# Sheet_1.net
KiCad netlist of a schematic drawn in EasyEDA
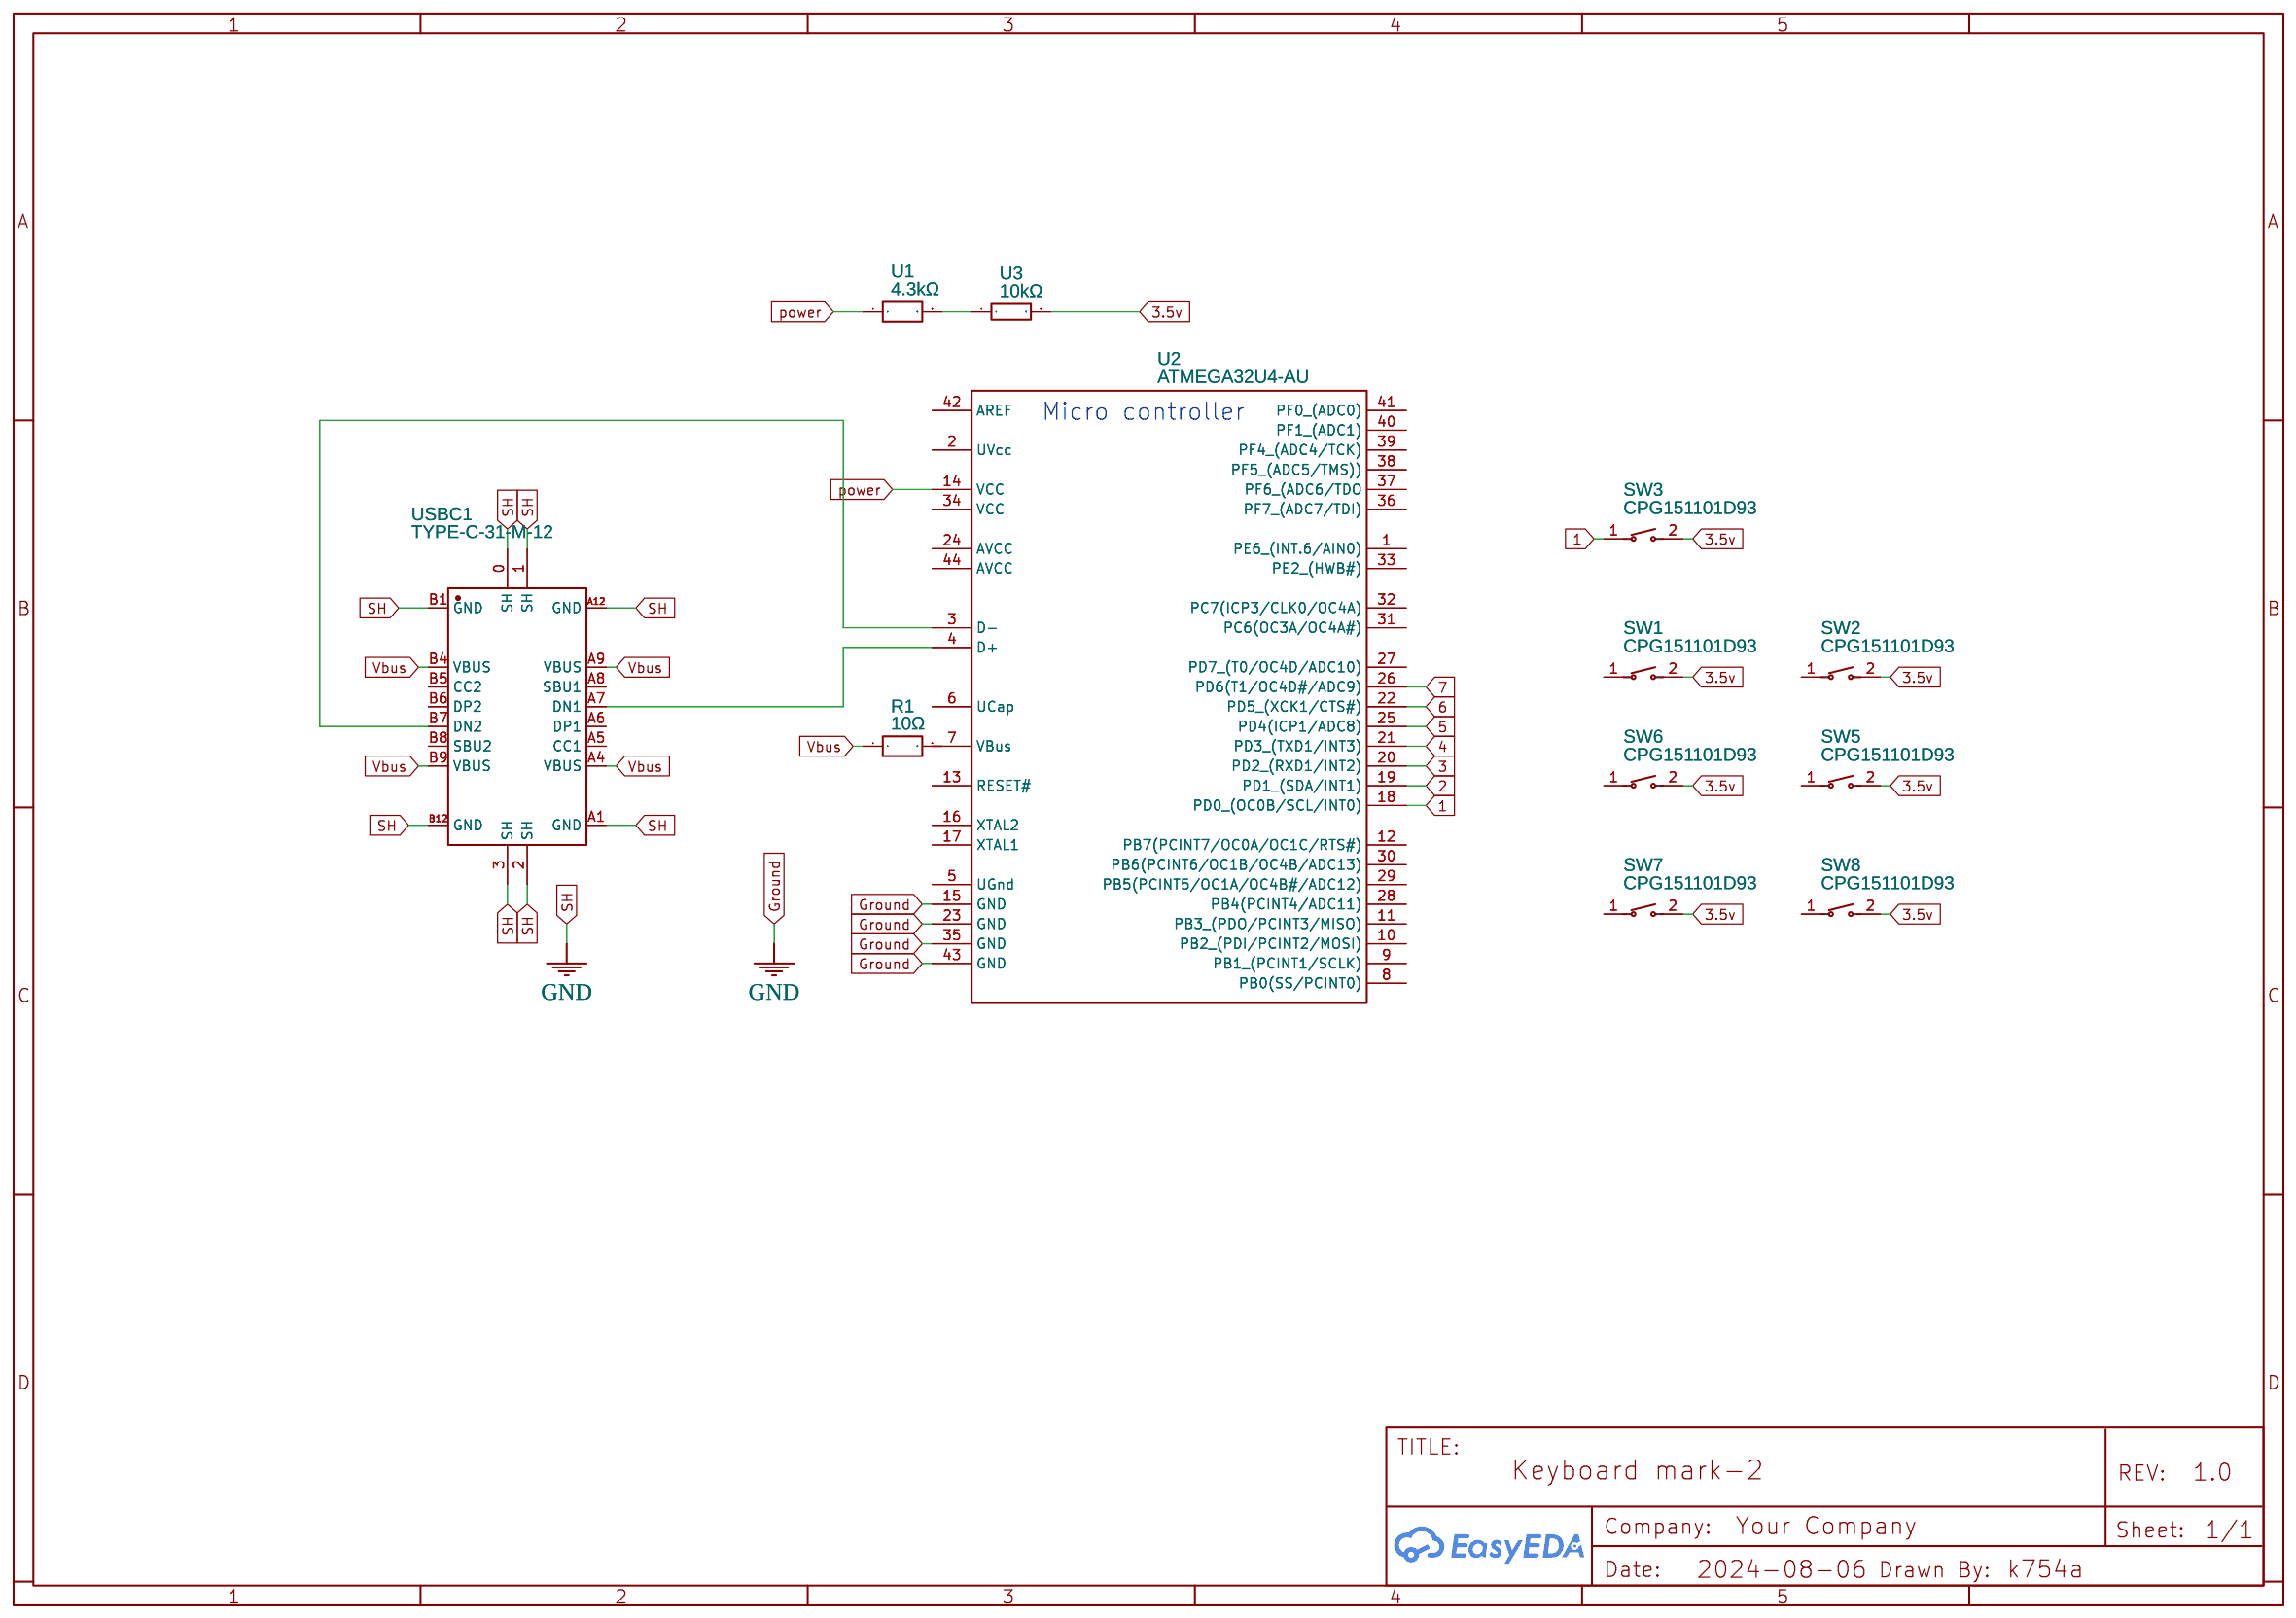
[diagram p0: schematic sheet]

(export (version "E")
  (design (tool "Eeschema 10.0.6"))
  (components
    (comp (ref "R1")
      (value "10Ω")
      (fields (field (name "Manufacturer Part") "CR1W-4K7±5%-TT63") (field (name "Manufacturer") "VO(翔胜)"))
      (libsource (lib "") (part "10Ω_1W"))
    )
    (comp (ref "SW1")
      (value "CPG151101D93")
      (fields (field (name "Manufacturer") "Kailh(凯华)"))
      (libsource (lib "") (part "CPG151101D93"))
    )
    (comp (ref "SW2")
      (value "CPG151101D93")
      (fields (field (name "Manufacturer") "Kailh(凯华)"))
      (libsource (lib "") (part "CPG151101D93"))
    )
    (comp (ref "SW3")
      (value "CPG151101D93")
      (fields (field (name "Manufacturer") "Kailh(凯华)"))
      (libsource (lib "") (part "CPG151101D93"))
    )
    (comp (ref "SW5")
      (value "CPG151101D93")
      (fields (field (name "Manufacturer") "Kailh(凯华)"))
      (libsource (lib "") (part "CPG151101D93"))
    )
    (comp (ref "SW6")
      (value "CPG151101D93")
      (fields (field (name "Manufacturer") "Kailh(凯华)"))
      (libsource (lib "") (part "CPG151101D93"))
    )
    (comp (ref "SW7")
      (value "CPG151101D93")
      (fields (field (name "Manufacturer") "Kailh(凯华)"))
      (libsource (lib "") (part "CPG151101D93"))
    )
    (comp (ref "SW8")
      (value "CPG151101D93")
      (fields (field (name "Manufacturer") "Kailh(凯华)"))
      (libsource (lib "") (part "CPG151101D93"))
    )
    (comp (ref "U1")
      (value "4.3kΩ")
      (fields (field (name "Manufacturer Part") "CR1/8W-4K3±5%-OT52") (field (name "Manufacturer") "VO(翔胜)"))
      (libsource (lib "") (part "CR1/8W-4K3±5%-OT52"))
    )
    (comp (ref "U2")
      (value "ATMEGA32U4-AU")
      (fields (field (name "Manufacturer") "MICROCHIP(美国微芯)"))
      (libsource (lib "") (part "ATMEGA32U4-AU"))
    )
    (comp (ref "U3")
      (value "10kΩ")
      (fields (field (name "Manufacturer Part") "HV73V1JTTD1002F") (field (name "Manufacturer") "KOA"))
      (libsource (lib "") (part "HV73V1JTTD1002F"))
    )
    (comp (ref "USBC1")
      (value "TYPE-C-31-M-12")
      (fields (field (name "Manufacturer") "韩国韩荣"))
      (libsource (lib "") (part "TYPE-C-31-M-12"))
    )
  )
  (nets
    (net (code "1") (name "1") (class "Default")
      (node (ref "SW3") (pin "1") (pinfunction "1_1") (pintype "unspecified"))
      (node (ref "U2") (pin "18") (pinfunction "PD0_(OC0B/SCL/INT0)_18") (pintype "bidirectional"))
    )
    (net (code "2") (name "2") (class "Default")
      (node (ref "U2") (pin "19") (pinfunction "PD1_(SDA/INT1)_19") (pintype "bidirectional"))
    )
    (net (code "3") (name "3") (class "Default")
      (node (ref "U2") (pin "20") (pinfunction "PD2_(RXD1/INT2)_20") (pintype "bidirectional"))
    )
    (net (code "4") (name "3.5v") (class "Default")
      (node (ref "SW1") (pin "2") (pinfunction "2_2") (pintype "unspecified"))
      (node (ref "SW2") (pin "2") (pinfunction "2_2") (pintype "unspecified"))
      (node (ref "SW3") (pin "2") (pinfunction "2_2") (pintype "unspecified"))
      (node (ref "SW5") (pin "2") (pinfunction "2_2") (pintype "unspecified"))
      (node (ref "SW6") (pin "2") (pinfunction "2_2") (pintype "unspecified"))
      (node (ref "SW7") (pin "2") (pinfunction "2_2") (pintype "unspecified"))
      (node (ref "SW8") (pin "2") (pinfunction "2_2") (pintype "unspecified"))
      (node (ref "U3") (pin "2") (pinfunction "2_2") (pintype "unspecified"))
    )
    (net (code "5") (name "4") (class "Default")
      (node (ref "U2") (pin "21") (pinfunction "PD3_(TXD1/INT3)_21") (pintype "bidirectional"))
    )
    (net (code "6") (name "5") (class "Default")
      (node (ref "U2") (pin "25") (pinfunction "PD4(ICP1/ADC8)_25") (pintype "bidirectional"))
    )
    (net (code "7") (name "6") (class "Default")
      (node (ref "U2") (pin "22") (pinfunction "PD5_(XCK1/CTS#)_22") (pintype "bidirectional"))
    )
    (net (code "8") (name "7") (class "Default")
      (node (ref "U2") (pin "26") (pinfunction "PD6(T1/OC4D#/ADC9)_26") (pintype "bidirectional"))
    )
    (net (code "9") (name "Ground") (class "Default")
      (node (ref "U2") (pin "15") (pinfunction "GND_15") (pintype "passive"))
      (node (ref "U2") (pin "23") (pinfunction "GND_23") (pintype "passive"))
      (node (ref "U2") (pin "35") (pinfunction "GND_35") (pintype "passive"))
      (node (ref "U2") (pin "43") (pinfunction "GND_43") (pintype "passive"))
      (node (ref "USBC1") (pin "0") (pinfunction "SH_0") (pintype "unspecified"))
      (node (ref "USBC1") (pin "1") (pinfunction "SH_1") (pintype "unspecified"))
      (node (ref "USBC1") (pin "2") (pinfunction "SH_2") (pintype "unspecified"))
      (node (ref "USBC1") (pin "3") (pinfunction "SH_3") (pintype "unspecified"))
      (node (ref "USBC1") (pin "A1") (pinfunction "GND_A1") (pintype "unspecified"))
      (node (ref "USBC1") (pin "A12") (pinfunction "GND_A12") (pintype "unspecified"))
      (node (ref "USBC1") (pin "B1") (pinfunction "GND_B1") (pintype "unspecified"))
      (node (ref "USBC1") (pin "B12") (pinfunction "GND_B12") (pintype "unspecified"))
    )
    (net (code "10") (name "Net-(U1-Pad2)") (class "Default")
      (node (ref "U1") (pin "2") (pinfunction "2_2") (pintype "unspecified"))
      (node (ref "U3") (pin "1") (pinfunction "1_1") (pintype "unspecified"))
    )
    (net (code "11") (name "Net-(U2-D+)") (class "Default")
      (node (ref "U2") (pin "4") (pinfunction "D+_4") (pintype "bidirectional"))
      (node (ref "USBC1") (pin "A7") (pinfunction "DN1_A7") (pintype "unspecified"))
    )
    (net (code "12") (name "Net-(U2-D-)") (class "Default")
      (node (ref "U2") (pin "3") (pinfunction "D-_3") (pintype "bidirectional"))
      (node (ref "USBC1") (pin "B7") (pinfunction "DN2_B7") (pintype "unspecified"))
    )
    (net (code "13") (name "Net-(U2-VBus)") (class "Default")
      (node (ref "R1") (pin "2") (pinfunction "2_2") (pintype "unspecified"))
      (node (ref "U2") (pin "7") (pinfunction "VBus_7") (pintype "unspecified"))
    )
    (net (code "14") (name "Vbus") (class "Default")
      (node (ref "R1") (pin "1") (pinfunction "1_1") (pintype "unspecified"))
      (node (ref "USBC1") (pin "A4") (pinfunction "VBUS_A4") (pintype "unspecified"))
      (node (ref "USBC1") (pin "A9") (pinfunction "VBUS_A9") (pintype "unspecified"))
      (node (ref "USBC1") (pin "B4") (pinfunction "VBUS_B4") (pintype "unspecified"))
      (node (ref "USBC1") (pin "B9") (pinfunction "VBUS_B9") (pintype "unspecified"))
    )
    (net (code "15") (name "power") (class "Default")
      (node (ref "U1") (pin "1") (pinfunction "1_1") (pintype "unspecified"))
      (node (ref "U2") (pin "14") (pinfunction "VCC_14") (pintype "passive"))
    )
    (net (code "16") (name "unconnected-(SW1-Pad1)") (class "Default")
      (node (ref "SW1") (pin "1") (pinfunction "1_1") (pintype "unspecified"))
    )
    (net (code "17") (name "unconnected-(SW2-Pad1)") (class "Default")
      (node (ref "SW2") (pin "1") (pinfunction "1_1") (pintype "unspecified"))
    )
    (net (code "18") (name "unconnected-(SW5-Pad1)") (class "Default")
      (node (ref "SW5") (pin "1") (pinfunction "1_1") (pintype "unspecified"))
    )
    (net (code "19") (name "unconnected-(SW6-Pad1)") (class "Default")
      (node (ref "SW6") (pin "1") (pinfunction "1_1") (pintype "unspecified"))
    )
    (net (code "20") (name "unconnected-(SW7-Pad1)") (class "Default")
      (node (ref "SW7") (pin "1") (pinfunction "1_1") (pintype "unspecified"))
    )
    (net (code "21") (name "unconnected-(SW8-Pad1)") (class "Default")
      (node (ref "SW8") (pin "1") (pinfunction "1_1") (pintype "unspecified"))
    )
    (net (code "22") (name "unconnected-(U2-AREF-Pad42)") (class "Default")
      (node (ref "U2") (pin "42") (pinfunction "AREF_42") (pintype "unspecified"))
    )
    (net (code "23") (name "unconnected-(U2-AVCC-Pad24)") (class "Default")
      (node (ref "U2") (pin "24") (pinfunction "AVCC_24") (pintype "passive"))
    )
    (net (code "24") (name "unconnected-(U2-AVCC-Pad44)") (class "Default")
      (node (ref "U2") (pin "44") (pinfunction "AVCC_44") (pintype "passive"))
    )
    (net (code "25") (name "unconnected-(U2-PB0(SS{slash}PCINT0)-Pad8)") (class "Default")
      (node (ref "U2") (pin "8") (pinfunction "PB0(SS/PCINT0)_8") (pintype "bidirectional"))
    )
    (net (code "26") (name "unconnected-(U2-PB1_(PCINT1{slash}SCLK)-Pad9)") (class "Default")
      (node (ref "U2") (pin "9") (pinfunction "PB1_(PCINT1/SCLK)_9") (pintype "bidirectional"))
    )
    (net (code "27") (name "unconnected-(U2-PB2_(PDI{slash}PCINT2{slash}MOSI)-Pad10)") (class "Default")
      (node (ref "U2") (pin "10") (pinfunction "PB2_(PDI/PCINT2/MOSI)_10") (pintype "bidirectional"))
    )
    (net (code "28") (name "unconnected-(U2-PB3_(PDO{slash}PCINT3{slash}MISO)-Pad11)") (class "Default")
      (node (ref "U2") (pin "11") (pinfunction "PB3_(PDO/PCINT3/MISO)_11") (pintype "bidirectional"))
    )
    (net (code "29") (name "unconnected-(U2-PB4(PCINT4{slash}ADC11)-Pad28)") (class "Default")
      (node (ref "U2") (pin "28") (pinfunction "PB4(PCINT4/ADC11)_28") (pintype "bidirectional"))
    )
    (net (code "30") (name "unconnected-(U2-PB5(PCINT5{slash}OC1A{slash}OC4B#{slash}ADC12)-Pad29)") (class "Default")
      (node (ref "U2") (pin "29") (pinfunction "PB5(PCINT5/OC1A/OC4B#/ADC12)_29") (pintype "bidirectional"))
    )
    (net (code "31") (name "unconnected-(U2-PB6(PCINT6{slash}OC1B{slash}OC4B{slash}ADC13)-Pad30)") (class "Default")
      (node (ref "U2") (pin "30") (pinfunction "PB6(PCINT6/OC1B/OC4B/ADC13)_30") (pintype "bidirectional"))
    )
    (net (code "32") (name "unconnected-(U2-PB7(PCINT7{slash}OC0A{slash}OC1C{slash}RTS#)-Pad12)") (class "Default")
      (node (ref "U2") (pin "12") (pinfunction "PB7(PCINT7/OC0A/OC1C/RTS#)_12") (pintype "bidirectional"))
    )
    (net (code "33") (name "unconnected-(U2-PC6(OC3A{slash}OC4A#)-Pad31)") (class "Default")
      (node (ref "U2") (pin "31") (pinfunction "PC6(OC3A/OC4A#)_31") (pintype "bidirectional"))
    )
    (net (code "34") (name "unconnected-(U2-PC7(ICP3{slash}CLK0{slash}OC4A)-Pad32)") (class "Default")
      (node (ref "U2") (pin "32") (pinfunction "PC7(ICP3/CLK0/OC4A)_32") (pintype "bidirectional"))
    )
    (net (code "35") (name "unconnected-(U2-PD7_(T0{slash}OC4D{slash}ADC10)-Pad27)") (class "Default")
      (node (ref "U2") (pin "27") (pinfunction "PD7_(T0/OC4D/ADC10)_27") (pintype "bidirectional"))
    )
    (net (code "36") (name "unconnected-(U2-PE2_(HWB#)-Pad33)") (class "Default")
      (node (ref "U2") (pin "33") (pinfunction "PE2_(HWB#)_33") (pintype "bidirectional"))
    )
    (net (code "37") (name "unconnected-(U2-PE6_(INT.6{slash}AIN0)-Pad1)") (class "Default")
      (node (ref "U2") (pin "1") (pinfunction "PE6_(INT.6/AIN0)_1") (pintype "bidirectional"))
    )
    (net (code "38") (name "unconnected-(U2-PF0_(ADC0)-Pad41)") (class "Default")
      (node (ref "U2") (pin "41") (pinfunction "PF0_(ADC0)_41") (pintype "bidirectional"))
    )
    (net (code "39") (name "unconnected-(U2-PF1_(ADC1)-Pad40)") (class "Default")
      (node (ref "U2") (pin "40") (pinfunction "PF1_(ADC1)_40") (pintype "bidirectional"))
    )
    (net (code "40") (name "unconnected-(U2-PF4_(ADC4{slash}TCK)-Pad39)") (class "Default")
      (node (ref "U2") (pin "39") (pinfunction "PF4_(ADC4/TCK)_39") (pintype "bidirectional"))
    )
    (net (code "41") (name "unconnected-(U2-PF5_(ADC5{slash}TMS))-Pad38)") (class "Default")
      (node (ref "U2") (pin "38") (pinfunction "PF5_(ADC5/TMS))_38") (pintype "bidirectional"))
    )
    (net (code "42") (name "unconnected-(U2-PF6_(ADC6{slash}TDO-Pad37)") (class "Default")
      (node (ref "U2") (pin "37") (pinfunction "PF6_(ADC6/TDO_37") (pintype "bidirectional"))
    )
    (net (code "43") (name "unconnected-(U2-PF7_(ADC7{slash}TDI)-Pad36)") (class "Default")
      (node (ref "U2") (pin "36") (pinfunction "PF7_(ADC7/TDI)_36") (pintype "bidirectional"))
    )
    (net (code "44") (name "unconnected-(U2-RESET#-Pad13)") (class "Default")
      (node (ref "U2") (pin "13") (pinfunction "RESET#_13") (pintype "unspecified"))
    )
    (net (code "45") (name "unconnected-(U2-UCap-Pad6)") (class "Default")
      (node (ref "U2") (pin "6") (pinfunction "UCap_6") (pintype "unspecified"))
    )
    (net (code "46") (name "unconnected-(U2-UGnd-Pad5)") (class "Default")
      (node (ref "U2") (pin "5") (pinfunction "UGnd_5") (pintype "passive"))
    )
    (net (code "47") (name "unconnected-(U2-UVcc-Pad2)") (class "Default")
      (node (ref "U2") (pin "2") (pinfunction "UVcc_2") (pintype "passive"))
    )
    (net (code "48") (name "unconnected-(U2-VCC-Pad34)") (class "Default")
      (node (ref "U2") (pin "34") (pinfunction "VCC_34") (pintype "passive"))
    )
    (net (code "49") (name "unconnected-(U2-XTAL1-Pad17)") (class "Default")
      (node (ref "U2") (pin "17") (pinfunction "XTAL1_17") (pintype "unspecified"))
    )
    (net (code "50") (name "unconnected-(U2-XTAL2-Pad16)") (class "Default")
      (node (ref "U2") (pin "16") (pinfunction "XTAL2_16") (pintype "output"))
    )
    (net (code "51") (name "unconnected-(USBC1-CC1-PadA5)") (class "Default")
      (node (ref "USBC1") (pin "A5") (pinfunction "CC1_A5") (pintype "unspecified"))
    )
    (net (code "52") (name "unconnected-(USBC1-CC2-PadB5)") (class "Default")
      (node (ref "USBC1") (pin "B5") (pinfunction "CC2_B5") (pintype "unspecified"))
    )
    (net (code "53") (name "unconnected-(USBC1-DP1-PadA6)") (class "Default")
      (node (ref "USBC1") (pin "A6") (pinfunction "DP1_A6") (pintype "unspecified"))
    )
    (net (code "54") (name "unconnected-(USBC1-DP2-PadB6)") (class "Default")
      (node (ref "USBC1") (pin "B6") (pinfunction "DP2_B6") (pintype "unspecified"))
    )
    (net (code "55") (name "unconnected-(USBC1-SBU1-PadA8)") (class "Default")
      (node (ref "USBC1") (pin "A8") (pinfunction "SBU1_A8") (pintype "unspecified"))
    )
    (net (code "56") (name "unconnected-(USBC1-SBU2-PadB8)") (class "Default")
      (node (ref "USBC1") (pin "B8") (pinfunction "SBU2_B8") (pintype "unspecified"))
    )
  )
)
